# Encoder_Fin_ARM_-_MCU_KL05_TQFP_48.net
KiCad netlist of a schematic drawn in Altium Designer
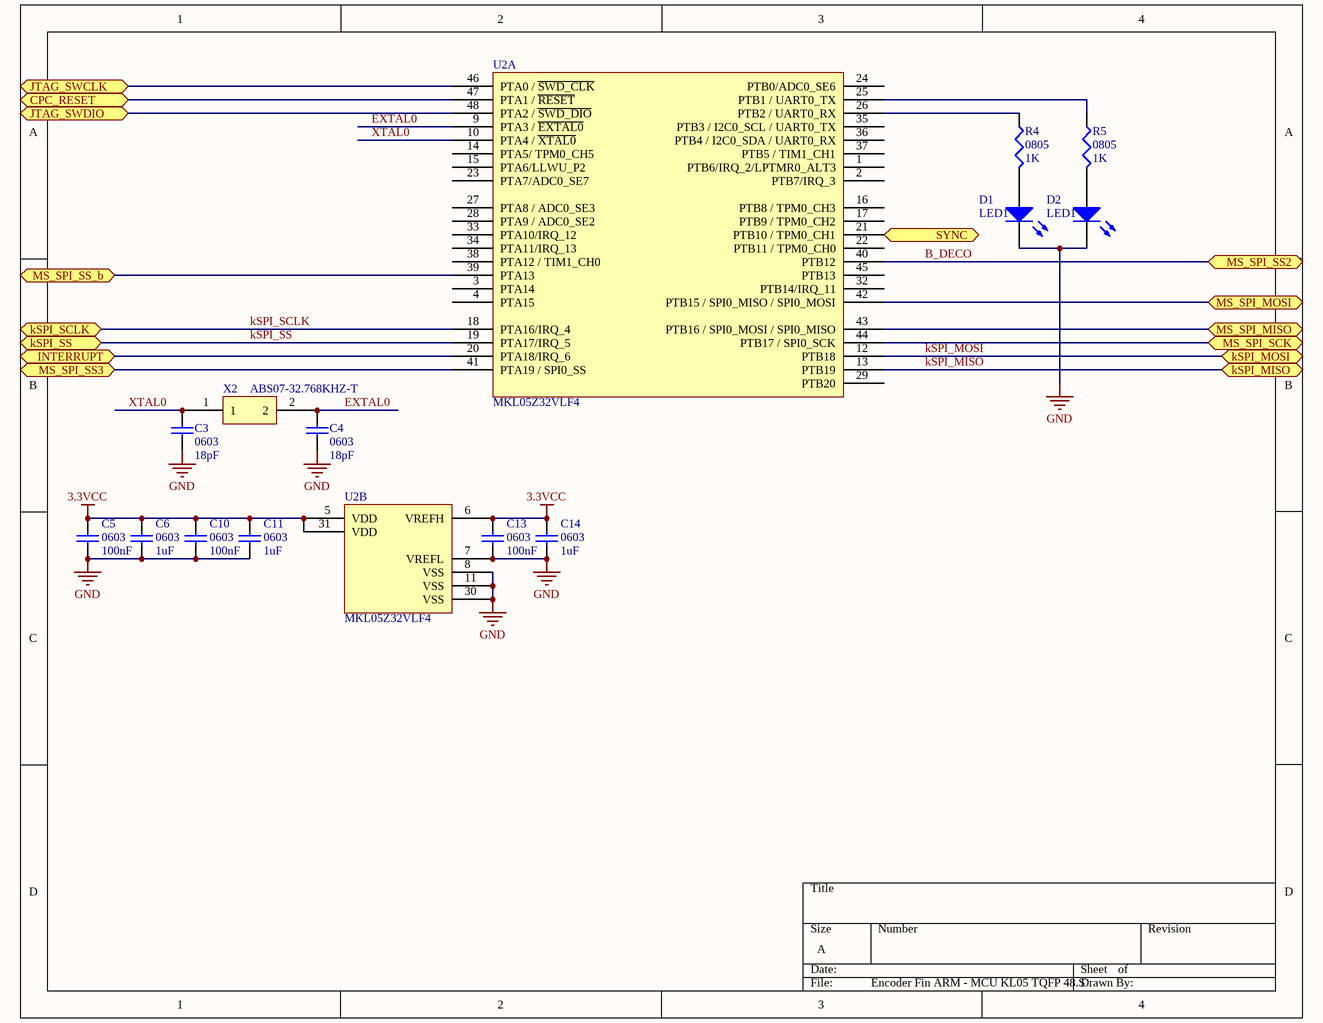
[diagram p0: Encoder Fin ARM - MCU KL05 TQFP 48.SchDoc]

(export (version "E")
  (design (tool "Eeschema 10.0.6"))
  (components
    (comp (ref "C3")
      (value "0603")
      (footprint "1608[0603]")
      (description "Capacitor (Semiconductor SIM Model)")
      (fields (field (name "ALTIUM_VALUE") "18pF") (field (name "PUBLISHER") "Altium Limited"))
      (libsource (lib "Miscellaneous Devices") (part "Cap Semi"))
    )
    (comp (ref "C4")
      (value "0603")
      (footprint "1608[0603]")
      (description "Capacitor (Semiconductor SIM Model)")
      (fields (field (name "ALTIUM_VALUE") "18pF") (field (name "PUBLISHER") "Altium Limited"))
      (libsource (lib "Miscellaneous Devices") (part "Cap Semi"))
    )
    (comp (ref "C5")
      (value "0603")
      (footprint "1608[0603]")
      (description "Capacitor (Semiconductor SIM Model)")
      (fields (field (name "ALTIUM_VALUE") "100nF") (field (name "PUBLISHER") "Altium Limited"))
      (libsource (lib "Miscellaneous Devices") (part "Cap Semi"))
    )
    (comp (ref "C6")
      (value "0603")
      (footprint "1608[0603]")
      (description "Capacitor (Semiconductor SIM Model)")
      (fields (field (name "ALTIUM_VALUE") "1uF") (field (name "PUBLISHER") "Altium Limited"))
      (libsource (lib "Miscellaneous Devices") (part "Cap Semi"))
    )
    (comp (ref "C10")
      (value "0603")
      (footprint "1608[0603]")
      (description "Capacitor (Semiconductor SIM Model)")
      (fields (field (name "ALTIUM_VALUE") "100nF") (field (name "PUBLISHER") "Altium Limited"))
      (libsource (lib "Miscellaneous Devices") (part "Cap Semi"))
    )
    (comp (ref "C11")
      (value "0603")
      (footprint "1608[0603]")
      (description "Capacitor (Semiconductor SIM Model)")
      (fields (field (name "ALTIUM_VALUE") "1uF") (field (name "PUBLISHER") "Altium Limited"))
      (libsource (lib "Miscellaneous Devices") (part "Cap Semi"))
    )
    (comp (ref "C13")
      (value "0603")
      (footprint "1608[0603]")
      (description "Capacitor (Semiconductor SIM Model)")
      (fields (field (name "ALTIUM_VALUE") "100nF") (field (name "PUBLISHER") "Altium Limited"))
      (libsource (lib "Miscellaneous Devices") (part "Cap Semi"))
    )
    (comp (ref "C14")
      (value "0603")
      (footprint "1608[0603]")
      (description "Capacitor (Semiconductor SIM Model)")
      (fields (field (name "ALTIUM_VALUE") "1uF") (field (name "PUBLISHER") "Altium Limited"))
      (libsource (lib "Miscellaneous Devices") (part "Cap Semi"))
    )
    (comp (ref "D1")
      (value "LED1")
      (footprint "SM 0805 polarized")
      (description "Typical RED GaAs LED")
      (fields (field (name "PUBLISHER") "Altium Limited"))
      (libsource (lib "Miscellaneous Devices") (part "LED1"))
    )
    (comp (ref "D2")
      (value "LED1")
      (footprint "SM 0805 polarized")
      (description "Typical RED GaAs LED")
      (fields (field (name "PUBLISHER") "Altium Limited"))
      (libsource (lib "Miscellaneous Devices") (part "LED1"))
    )
    (comp (ref "R4")
      (value "0805")
      (footprint "SM 0805 - gap trimmed")
      (description "Resistor")
      (fields (field (name "ALTIUM_VALUE") "1K") (field (name "PUBLISHER") "Altium Limited"))
      (libsource (lib "Miscellaneous Devices") (part "Res3"))
    )
    (comp (ref "R5")
      (value "0805")
      (footprint "SM 0805 - gap trimmed")
      (description "Resistor")
      (fields (field (name "ALTIUM_VALUE") "1K") (field (name "PUBLISHER") "Altium Limited"))
      (libsource (lib "Miscellaneous Devices") (part "Res3"))
    )
    (comp (ref "U2")
      (value "MKL05Z32VLF4")
      (footprint "MKL05Z32VLF4")
      (description "ARM Cortex M0+")
      (libsource (lib "ExtruderFinLib") (part "MKL05Z32VLF4"))
    )
    (comp (ref "X2")
      (value "ABS07-32.768KHZ-T")
      (footprint "ABS07-32.768KHZ-T")
      (description "ABS07-32.768KHZ-T RTC Crystal Oscillator")
      (libsource (lib "Adams Altium Library") (part "ABS07-32.768KHZ-T"))
    )
  )
  (nets
    (net (code "1") (name "/B_DECO") (class "Default")
      (node (ref "U2") (pin "40") (pinfunction "PTB12_40") (pintype "passive"))
    )
    (net (code "2") (name "/CPC_RESET") (class "Default")
      (node (ref "U2") (pin "47") (pinfunction "PTA1_/_~{RESET}_47") (pintype "passive"))
    )
    (net (code "3") (name "/EXTAL0") (class "Default")
      (node (ref "C4") (pin "1") (pinfunction "1_1") (pintype "passive"))
      (node (ref "U2") (pin "9") (pinfunction "PTA3_/_~{EXTAL0}_9") (pintype "passive"))
      (node (ref "X2") (pin "2") (pinfunction "2_2") (pintype "passive"))
    )
    (net (code "4") (name "/INTERRUPT") (class "Default")
      (node (ref "U2") (pin "20") (pinfunction "PTA18/IRQ_6_20") (pintype "passive"))
    )
    (net (code "5") (name "/JTAG_SWCLK") (class "Default")
      (node (ref "U2") (pin "46") (pinfunction "PTA0_/_~{SWD_CLK}_46") (pintype "passive"))
    )
    (net (code "6") (name "/JTAG_SWDIO") (class "Default")
      (node (ref "U2") (pin "48") (pinfunction "PTA2_/_~{SWD_DIO}_48") (pintype "passive"))
    )
    (net (code "7") (name "/MS_SPI_MISO") (class "Default")
      (node (ref "U2") (pin "43") (pinfunction "PTB16_/_SPI0_MOSI_/_SPI0_MISO_43") (pintype "passive"))
    )
    (net (code "8") (name "/MS_SPI_MOSI") (class "Default")
      (node (ref "U2") (pin "42") (pinfunction "PTB15_/_SPI0_MISO_/_SPI0_MOSI_42") (pintype "passive"))
    )
    (net (code "9") (name "/MS_SPI_SCK") (class "Default")
      (node (ref "U2") (pin "44") (pinfunction "PTB17_/_SPI0_SCK_44") (pintype "passive"))
    )
    (net (code "10") (name "/MS_SPI_SS3") (class "Default")
      (node (ref "U2") (pin "41") (pinfunction "PTA19_/_SPI0_SS_41") (pintype "passive"))
    )
    (net (code "11") (name "/MS_SPI_SS_b") (class "Default")
      (node (ref "U2") (pin "39") (pinfunction "PTA13_39") (pintype "passive"))
    )
    (net (code "12") (name "/SYNC") (class "Default")
      (node (ref "U2") (pin "21") (pinfunction "PTB10_/_TPM0_CH1_21") (pintype "passive"))
    )
    (net (code "13") (name "/XTAL0") (class "Default")
      (node (ref "C3") (pin "1") (pinfunction "1_1") (pintype "passive"))
      (node (ref "U2") (pin "10") (pinfunction "PTA4_/_~{XTAL0}_10") (pintype "passive"))
      (node (ref "X2") (pin "1") (pinfunction "1_1") (pintype "passive"))
    )
    (net (code "14") (name "/kSPI_MISO") (class "Default")
      (node (ref "U2") (pin "13") (pinfunction "PTB19_13") (pintype "passive"))
    )
    (net (code "15") (name "/kSPI_MOSI") (class "Default")
      (node (ref "U2") (pin "12") (pinfunction "PTB18_12") (pintype "passive"))
    )
    (net (code "16") (name "/kSPI_SCLK") (class "Default")
      (node (ref "U2") (pin "18") (pinfunction "PTA16/IRQ_4_18") (pintype "passive"))
    )
    (net (code "17") (name "/kSPI_SS") (class "Default")
      (node (ref "U2") (pin "19") (pinfunction "PTA17/IRQ_5_19") (pintype "passive"))
    )
    (net (code "18") (name "3.3VCC") (class "Default")
      (node (ref "C10") (pin "2") (pinfunction "2_2") (pintype "passive"))
      (node (ref "C11") (pin "2") (pinfunction "2_2") (pintype "passive"))
      (node (ref "C13") (pin "1") (pinfunction "1_1") (pintype "passive"))
      (node (ref "C14") (pin "1") (pinfunction "1_1") (pintype "passive"))
      (node (ref "C5") (pin "2") (pinfunction "2_2") (pintype "passive"))
      (node (ref "C6") (pin "2") (pinfunction "2_2") (pintype "passive"))
      (node (ref "U2") (pin "31") (pinfunction "VDD_31") (pintype "passive"))
      (node (ref "U2") (pin "5") (pinfunction "VDD_5") (pintype "passive"))
      (node (ref "U2") (pin "6") (pinfunction "VREFH_6") (pintype "passive"))
    )
    (net (code "19") (name "GND") (class "Default")
      (node (ref "C10") (pin "1") (pinfunction "1_1") (pintype "passive"))
      (node (ref "C11") (pin "1") (pinfunction "1_1") (pintype "passive"))
      (node (ref "C13") (pin "2") (pinfunction "2_2") (pintype "passive"))
      (node (ref "C14") (pin "2") (pinfunction "2_2") (pintype "passive"))
      (node (ref "C3") (pin "2") (pinfunction "2_2") (pintype "passive"))
      (node (ref "C4") (pin "2") (pinfunction "2_2") (pintype "passive"))
      (node (ref "C5") (pin "1") (pinfunction "1_1") (pintype "passive"))
      (node (ref "C6") (pin "1") (pinfunction "1_1") (pintype "passive"))
      (node (ref "D1") (pin "1") (pinfunction "A_1") (pintype "passive"))
      (node (ref "D2") (pin "1") (pinfunction "A_1") (pintype "passive"))
      (node (ref "U2") (pin "11") (pinfunction "VSS_11") (pintype "passive"))
      (node (ref "U2") (pin "30") (pinfunction "VSS_30") (pintype "passive"))
      (node (ref "U2") (pin "7") (pinfunction "VREFL_7") (pintype "passive"))
      (node (ref "U2") (pin "8") (pinfunction "VSS_8") (pintype "passive"))
    )
    (net (code "20") (name "Net-(D1-K)") (class "Default")
      (node (ref "D1") (pin "2") (pinfunction "K_2") (pintype "passive"))
      (node (ref "R4") (pin "2") (pinfunction "2_2") (pintype "passive"))
    )
    (net (code "21") (name "Net-(D2-K)") (class "Default")
      (node (ref "D2") (pin "2") (pinfunction "K_2") (pintype "passive"))
      (node (ref "R5") (pin "2") (pinfunction "2_2") (pintype "passive"))
    )
    (net (code "22") (name "Net-(U2A-PTB1_{slash}_UART0_TX)") (class "Default")
      (node (ref "R5") (pin "1") (pinfunction "1_1") (pintype "passive"))
      (node (ref "U2") (pin "25") (pinfunction "PTB1_/_UART0_TX_25") (pintype "passive"))
    )
    (net (code "23") (name "Net-(U2A-PTB2_{slash}_UART0_RX)") (class "Default")
      (node (ref "R4") (pin "1") (pinfunction "1_1") (pintype "passive"))
      (node (ref "U2") (pin "26") (pinfunction "PTB2_/_UART0_RX_26") (pintype "passive"))
    )
    (net (code "24") (name "unconnected-(U2A-PTA5{slash}_TPM0_CH5-Pad14)") (class "Default")
      (node (ref "U2") (pin "14") (pinfunction "PTA5/_TPM0_CH5_14") (pintype "passive"))
    )
    (net (code "25") (name "unconnected-(U2A-PTA6{slash}LLWU_P2-Pad15)") (class "Default")
      (node (ref "U2") (pin "15") (pinfunction "PTA6/LLWU_P2_15") (pintype "passive"))
    )
    (net (code "26") (name "unconnected-(U2A-PTA7{slash}ADC0_SE7-Pad23)") (class "Default")
      (node (ref "U2") (pin "23") (pinfunction "PTA7/ADC0_SE7_23") (pintype "passive"))
    )
    (net (code "27") (name "unconnected-(U2A-PTA8_{slash}_ADC0_SE3-Pad27)") (class "Default")
      (node (ref "U2") (pin "27") (pinfunction "PTA8_/_ADC0_SE3_27") (pintype "passive"))
    )
    (net (code "28") (name "unconnected-(U2A-PTA9_{slash}_ADC0_SE2-Pad28)") (class "Default")
      (node (ref "U2") (pin "28") (pinfunction "PTA9_/_ADC0_SE2_28") (pintype "passive"))
    )
    (net (code "29") (name "unconnected-(U2A-PTA10{slash}IRQ_12-Pad33)") (class "Default")
      (node (ref "U2") (pin "33") (pinfunction "PTA10/IRQ_12_33") (pintype "passive"))
    )
    (net (code "30") (name "unconnected-(U2A-PTA11{slash}IRQ_13-Pad34)") (class "Default")
      (node (ref "U2") (pin "34") (pinfunction "PTA11/IRQ_13_34") (pintype "passive"))
    )
    (net (code "31") (name "unconnected-(U2A-PTA12_{slash}_TIM1_CH0-Pad38)") (class "Default")
      (node (ref "U2") (pin "38") (pinfunction "PTA12_/_TIM1_CH0_38") (pintype "passive"))
    )
    (net (code "32") (name "unconnected-(U2A-PTA14-Pad3)") (class "Default")
      (node (ref "U2") (pin "3") (pinfunction "PTA14_3") (pintype "passive"))
    )
    (net (code "33") (name "unconnected-(U2A-PTA15-Pad4)") (class "Default")
      (node (ref "U2") (pin "4") (pinfunction "PTA15_4") (pintype "passive"))
    )
    (net (code "34") (name "unconnected-(U2A-PTB0{slash}ADC0_SE6-Pad24)") (class "Default")
      (node (ref "U2") (pin "24") (pinfunction "PTB0/ADC0_SE6_24") (pintype "passive"))
    )
    (net (code "35") (name "unconnected-(U2A-PTB3_{slash}_I2C0_SCL_{slash}_UART0_TX-Pad35)") (class "Default")
      (node (ref "U2") (pin "35") (pinfunction "PTB3_/_I2C0_SCL_/_UART0_TX_35") (pintype "passive"))
    )
    (net (code "36") (name "unconnected-(U2A-PTB4_{slash}_I2C0_SDA_{slash}_UART0_RX-Pad36)") (class "Default")
      (node (ref "U2") (pin "36") (pinfunction "PTB4_/_I2C0_SDA_/_UART0_RX_36") (pintype "passive"))
    )
    (net (code "37") (name "unconnected-(U2A-PTB5_{slash}_TIM1_CH1-Pad37)") (class "Default")
      (node (ref "U2") (pin "37") (pinfunction "PTB5_/_TIM1_CH1_37") (pintype "passive"))
    )
    (net (code "38") (name "unconnected-(U2A-PTB6{slash}IRQ_2{slash}LPTMR0_ALT3-Pad1)") (class "Default")
      (node (ref "U2") (pin "1") (pinfunction "PTB6/IRQ_2/LPTMR0_ALT3_1") (pintype "passive"))
    )
    (net (code "39") (name "unconnected-(U2A-PTB7{slash}IRQ_3-Pad2)") (class "Default")
      (node (ref "U2") (pin "2") (pinfunction "PTB7/IRQ_3_2") (pintype "passive"))
    )
    (net (code "40") (name "unconnected-(U2A-PTB8_{slash}_TPM0_CH3-Pad16)") (class "Default")
      (node (ref "U2") (pin "16") (pinfunction "PTB8_/_TPM0_CH3_16") (pintype "passive"))
    )
    (net (code "41") (name "unconnected-(U2A-PTB9_{slash}_TPM0_CH2-Pad17)") (class "Default")
      (node (ref "U2") (pin "17") (pinfunction "PTB9_/_TPM0_CH2_17") (pintype "passive"))
    )
    (net (code "42") (name "unconnected-(U2A-PTB11_{slash}_TPM0_CH0-Pad22)") (class "Default")
      (node (ref "U2") (pin "22") (pinfunction "PTB11_/_TPM0_CH0_22") (pintype "passive"))
    )
    (net (code "43") (name "unconnected-(U2A-PTB13-Pad45)") (class "Default")
      (node (ref "U2") (pin "45") (pinfunction "PTB13_45") (pintype "passive"))
    )
    (net (code "44") (name "unconnected-(U2A-PTB14{slash}IRQ_11-Pad32)") (class "Default")
      (node (ref "U2") (pin "32") (pinfunction "PTB14/IRQ_11_32") (pintype "passive"))
    )
    (net (code "45") (name "unconnected-(U2A-PTB20-Pad29)") (class "Default")
      (node (ref "U2") (pin "29") (pinfunction "PTB20_29") (pintype "passive"))
    )
  )
)
